# trinamic-controller.net
KiCad netlist of a schematic drawn in Altium Designer
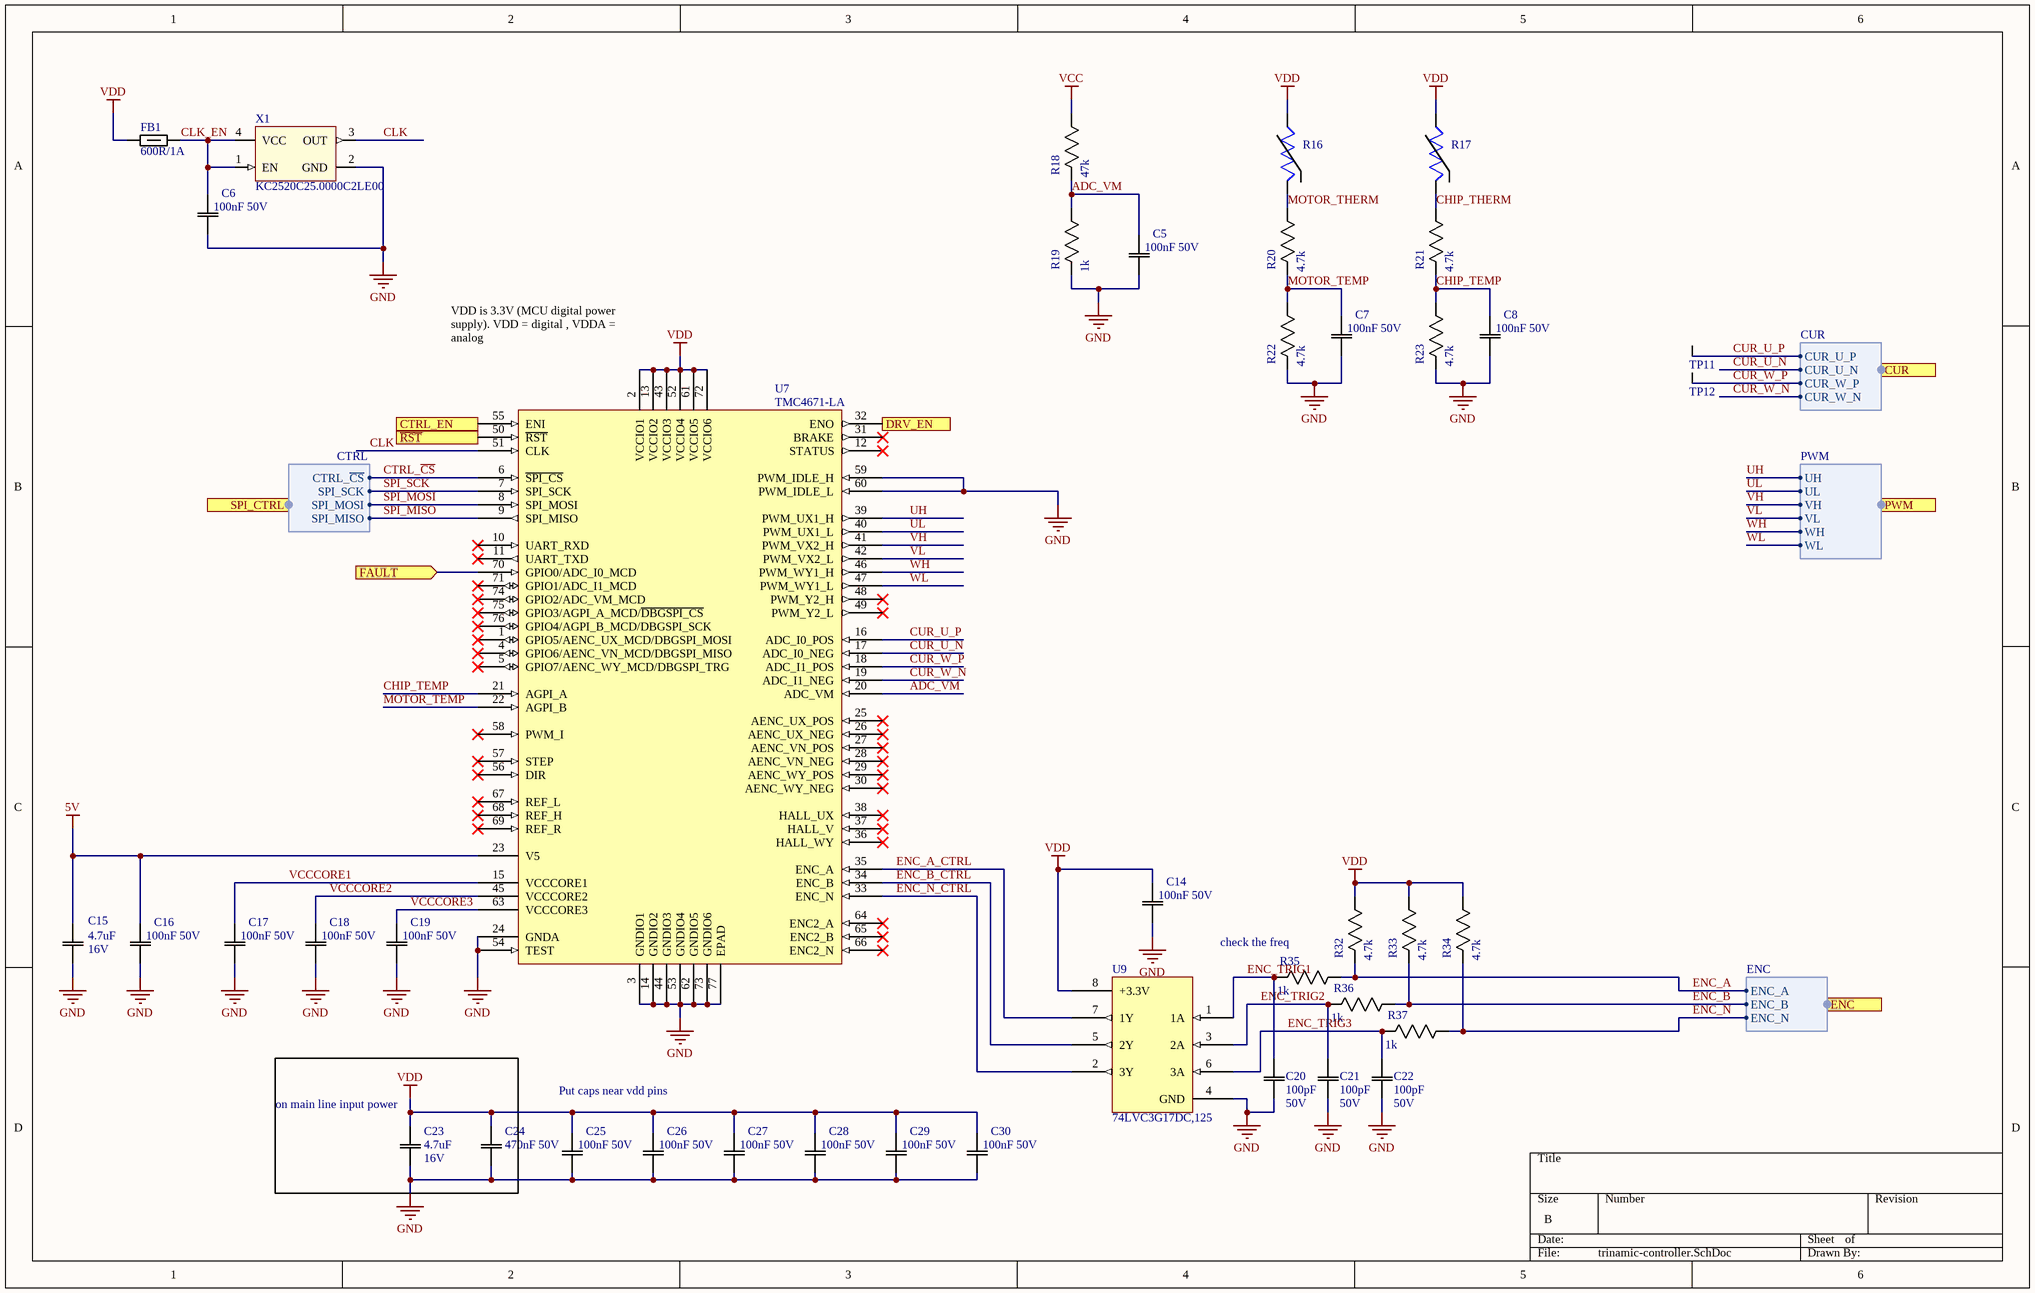
[diagram p0: trinamic-controller.SchDoc]

(export (version "E")
  (design (tool "Eeschema 10.0.6"))
  (components
    (comp (ref "C5")
      (value "100nF 50V")
      (footprint "0603")
      (description "Default Symbol for Capacitors")
      (fields (field (name "TOLERANCE") "10%") (field (name "PART NUMBER") "CAP 100nF 50V"))
      (libsource (lib "capacitor_library") (part "CAP_Default"))
    )
    (comp (ref "C6")
      (value "100nF 50V")
      (footprint "0603")
      (description "Default Symbol for Capacitors")
      (fields (field (name "TOLERANCE") "10%") (field (name "PART NUMBER") "CAP 100nF 50V"))
      (libsource (lib "capacitor_library") (part "CAP_Default"))
    )
    (comp (ref "C7")
      (value "100nF 50V")
      (footprint "0603")
      (description "Default Symbol for Capacitors")
      (fields (field (name "TOLERANCE") "10%") (field (name "PART NUMBER") "CAP 100nF 50V"))
      (libsource (lib "capacitor_library") (part "CAP_Default"))
    )
    (comp (ref "C8")
      (value "100nF 50V")
      (footprint "0603")
      (description "Default Symbol for Capacitors")
      (fields (field (name "TOLERANCE") "10%") (field (name "PART NUMBER") "CAP 100nF 50V"))
      (libsource (lib "capacitor_library") (part "CAP_Default"))
    )
    (comp (ref "C14")
      (value "100nF 50V")
      (footprint "0603")
      (description "Default Symbol for Capacitors")
      (fields (field (name "TOLERANCE") "10%") (field (name "PART NUMBER") "CAP 100nF 50V"))
      (libsource (lib "capacitor_library") (part "CAP_Default"))
    )
    (comp (ref "C15")
      (value "4.7uF")
      (footprint "0603")
      (description "Default Symbol for Capacitors")
      (fields
        (field (name "TOLERANCE") "10%")
        (field (name "RATING") "16V")
        (field (name "PART NUMBER") "CAP 4.7uF 16V")
      )
      (libsource (lib "capacitor_library") (part "CAP_Default"))
    )
    (comp (ref "C16")
      (value "100nF 50V")
      (footprint "0603")
      (description "Default Symbol for Capacitors")
      (fields (field (name "TOLERANCE") "10%") (field (name "PART NUMBER") "CAP 100nF 50V"))
      (libsource (lib "capacitor_library") (part "CAP_Default"))
    )
    (comp (ref "C17")
      (value "100nF 50V")
      (footprint "0603")
      (description "Default Symbol for Capacitors")
      (fields (field (name "TOLERANCE") "10%") (field (name "PART NUMBER") "CAP 100nF 50V"))
      (libsource (lib "capacitor_library") (part "CAP_Default"))
    )
    (comp (ref "C18")
      (value "100nF 50V")
      (footprint "0603")
      (description "Default Symbol for Capacitors")
      (fields (field (name "TOLERANCE") "10%") (field (name "PART NUMBER") "CAP 100nF 50V"))
      (libsource (lib "capacitor_library") (part "CAP_Default"))
    )
    (comp (ref "C19")
      (value "100nF 50V")
      (footprint "0603")
      (description "Default Symbol for Capacitors")
      (fields (field (name "TOLERANCE") "10%") (field (name "PART NUMBER") "CAP 100nF 50V"))
      (libsource (lib "capacitor_library") (part "CAP_Default"))
    )
    (comp (ref "C20")
      (value "100pF")
      (footprint "0603")
      (description "Default Symbol for Capacitors")
      (fields
        (field (name "TOLERANCE") "10%")
        (field (name "RATING") "50V")
        (field (name "PART NUMBER") "CAP 100pF 50V")
      )
      (libsource (lib "capacitor_library") (part "CAP_Default"))
    )
    (comp (ref "C21")
      (value "100pF")
      (footprint "0603")
      (description "Default Symbol for Capacitors")
      (fields
        (field (name "TOLERANCE") "10%")
        (field (name "RATING") "50V")
        (field (name "PART NUMBER") "CAP 100pF 50V")
      )
      (libsource (lib "capacitor_library") (part "CAP_Default"))
    )
    (comp (ref "C22")
      (value "100pF")
      (footprint "0603")
      (description "Default Symbol for Capacitors")
      (fields
        (field (name "TOLERANCE") "10%")
        (field (name "RATING") "50V")
        (field (name "PART NUMBER") "CAP 100pF 50V")
      )
      (libsource (lib "capacitor_library") (part "CAP_Default"))
    )
    (comp (ref "C23")
      (value "4.7uF")
      (footprint "0603")
      (description "Default Symbol for Capacitors")
      (fields
        (field (name "TOLERANCE") "10%")
        (field (name "RATING") "16V")
        (field (name "PART NUMBER") "CAP 4.7uF 16V")
      )
      (libsource (lib "capacitor_library") (part "CAP_Default"))
    )
    (comp (ref "C24")
      (value "470nF 50V")
      (footprint "0603")
      (description "Default Symbol for Capacitors")
      (fields (field (name "TOLERANCE") "10%") (field (name "PART NUMBER") "CAP 470nF 50V"))
      (libsource (lib "capacitor_library") (part "CAP_Default"))
    )
    (comp (ref "C25")
      (value "100nF 50V")
      (footprint "0603")
      (description "Default Symbol for Capacitors")
      (fields (field (name "TOLERANCE") "10%") (field (name "PART NUMBER") "CAP 100nF 50V"))
      (libsource (lib "capacitor_library") (part "CAP_Default"))
    )
    (comp (ref "C26")
      (value "100nF 50V")
      (footprint "0603")
      (description "Default Symbol for Capacitors")
      (fields (field (name "TOLERANCE") "10%") (field (name "PART NUMBER") "CAP 100nF 50V"))
      (libsource (lib "capacitor_library") (part "CAP_Default"))
    )
    (comp (ref "C27")
      (value "100nF 50V")
      (footprint "0603")
      (description "Default Symbol for Capacitors")
      (fields (field (name "TOLERANCE") "10%") (field (name "PART NUMBER") "CAP 100nF 50V"))
      (libsource (lib "capacitor_library") (part "CAP_Default"))
    )
    (comp (ref "C28")
      (value "100nF 50V")
      (footprint "0603")
      (description "Default Symbol for Capacitors")
      (fields (field (name "TOLERANCE") "10%") (field (name "PART NUMBER") "CAP 100nF 50V"))
      (libsource (lib "capacitor_library") (part "CAP_Default"))
    )
    (comp (ref "C29")
      (value "100nF 50V")
      (footprint "0603")
      (description "Default Symbol for Capacitors")
      (fields (field (name "TOLERANCE") "10%") (field (name "PART NUMBER") "CAP 100nF 50V"))
      (libsource (lib "capacitor_library") (part "CAP_Default"))
    )
    (comp (ref "C30")
      (value "100nF 50V")
      (footprint "0603")
      (description "Default Symbol for Capacitors")
      (fields (field (name "TOLERANCE") "10%") (field (name "PART NUMBER") "CAP 100nF 50V"))
      (libsource (lib "capacitor_library") (part "CAP_Default"))
    )
    (comp (ref "FB1")
      (value "600R/1A")
      (footprint "0603")
      (fields (field (name "PART NUMBER") "FERRITE BEAD 200 MOHM 0603 1LN"))
      (libsource (lib "Inductor_Library") (part "FERRITE BEAD 200 MOHM 0603 1LN"))
    )
    (comp (ref "R16")
      (value "RES NTC 10k")
      (footprint "THERMISTOR TH")
      (fields (field (name "PART NUMBER") "RES NTC 10k TH") (field (name "TOLERANCE") "1%"))
      (libsource (lib "Resistor_Library") (part "RES NTC 10k"))
    )
    (comp (ref "R17")
      (value "RES NTC 10k")
      (footprint "0603")
      (fields (field (name "PART NUMBER") "RES NTC 10k CHIP") (field (name "TOLERANCE") "1%"))
      (libsource (lib "Resistor_Library") (part "RES NTC 10k"))
    )
    (comp (ref "R18")
      (value "47k")
      (footprint "0603")
      (description "Default Resistor Symbol")
      (fields (field (name "TOLERANCE") "1%") (field (name "PART NUMBER") "RES 47k 1/8W - 1%"))
      (libsource (lib "Resistor_Library") (part "RES_DEFAULT"))
    )
    (comp (ref "R19")
      (value "1k")
      (footprint "0603")
      (description "Default Resistor Symbol")
      (fields (field (name "TOLERANCE") "1%") (field (name "PART NUMBER") "RES 1k 1/8W - 1%"))
      (libsource (lib "") (part "RES_DEFAULT_1"))
    )
    (comp (ref "R20")
      (value "4.7k")
      (footprint "0603")
      (description "Default Resistor Symbol")
      (fields (field (name "TOLERANCE") "1%") (field (name "PART NUMBER") "RES 4.7k 1/8W - 1%"))
      (libsource (lib "Resistor_Library") (part "RES_DEFAULT"))
    )
    (comp (ref "R21")
      (value "4.7k")
      (footprint "0603")
      (description "Default Resistor Symbol")
      (fields (field (name "TOLERANCE") "1%") (field (name "PART NUMBER") "RES 4.7k 1/8W - 1%"))
      (libsource (lib "Resistor_Library") (part "RES_DEFAULT"))
    )
    (comp (ref "R22")
      (value "4.7k")
      (footprint "0603")
      (description "Default Resistor Symbol")
      (fields (field (name "TOLERANCE") "1%") (field (name "PART NUMBER") "RES 4.7k 1/8W - 1%"))
      (libsource (lib "Resistor_Library") (part "RES_DEFAULT"))
    )
    (comp (ref "R23")
      (value "4.7k")
      (footprint "0603")
      (description "Default Resistor Symbol")
      (fields (field (name "TOLERANCE") "1%") (field (name "PART NUMBER") "RES 4.7k 1/8W - 1%"))
      (libsource (lib "Resistor_Library") (part "RES_DEFAULT"))
    )
    (comp (ref "R32")
      (value "4.7k")
      (footprint "0603")
      (description "Default Resistor Symbol")
      (fields (field (name "TOLERANCE") "5%") (field (name "PART NUMBER") "RES 4.7k 1/8W - 5%"))
      (libsource (lib "") (part "RES_DEFAULT_1"))
    )
    (comp (ref "R33")
      (value "4.7k")
      (footprint "0603")
      (description "Default Resistor Symbol")
      (fields (field (name "TOLERANCE") "5%") (field (name "PART NUMBER") "RES 4.7k 1/8W - 5%"))
      (libsource (lib "") (part "RES_DEFAULT_1"))
    )
    (comp (ref "R34")
      (value "4.7k")
      (footprint "0603")
      (description "Default Resistor Symbol")
      (fields (field (name "TOLERANCE") "5%") (field (name "PART NUMBER") "RES 4.7k 1/8W - 5%"))
      (libsource (lib "Resistor_Library") (part "RES_DEFAULT"))
    )
    (comp (ref "R35")
      (value "1k")
      (footprint "0603")
      (description "Default Resistor Symbol")
      (fields (field (name "TOLERANCE") "1%") (field (name "PART NUMBER") "RES 1k 1/8W - 1%"))
      (libsource (lib "Resistor_Library") (part "RES_DEFAULT"))
    )
    (comp (ref "R36")
      (value "1k")
      (footprint "0603")
      (description "Default Resistor Symbol")
      (fields (field (name "TOLERANCE") "1%") (field (name "PART NUMBER") "RES 1k 1/8W - 1%"))
      (libsource (lib "") (part "RES_DEFAULT_1"))
    )
    (comp (ref "R37")
      (value "1k")
      (footprint "0603")
      (description "Default Resistor Symbol")
      (fields (field (name "TOLERANCE") "1%") (field (name "PART NUMBER") "RES 1k 1/8W - 1%"))
      (libsource (lib "Resistor_Library") (part "RES_DEFAULT"))
    )
    (comp (ref "TP11")
      (value "C_U")
      (footprint "TP")
      (fields (field (name "PART NUMBER") "Test Point (Via)"))
      (libsource (lib "IC_Library") (part "Test Point (Via)"))
    )
    (comp (ref "TP12")
      (value "C_W")
      (footprint "TP")
      (fields (field (name "PART NUMBER") "Test Point (Via)"))
      (libsource (lib "IC_Library") (part "Test Point (Via)"))
    )
    (comp (ref "U7")
      (value "TMC4671-LA")
      (footprint "QFN40P1050X650X90_HS-77N")
      (description "Motor Driver, -40 To 125Deg C Rohs Compliant: Yes")
      (fields (field (name "PART NUMBER") "TMC4671"))
      (libsource (lib "IC_Library") (part "TMC4671"))
    )
    (comp (ref "U9")
      (value "74LVC3G17DC,125")
      (footprint "8-VSSOP")
      (description "IC BUFFER TRIPLE SCHMITT TRIGGER 5.5V VSSOP-8")
      (fields (field (name "PART NUMBER") "IC 74LVC3G17DC,125"))
      (libsource (lib "IC_Library") (part "IC 74LVC3G17DC,125"))
    )
    (comp (ref "X1")
      (value "KC2520C25.0000C2LE00")
      (footprint "KC2520C25.0000C2LE00")
      (description "Oscillator XO 25MHz ±15ppm 15pF CMOS 55% 2.5V/3.3V 4-Pin Mini-CSMD T/R")
      (fields (field (name "PART NUMBER") "XTAL OSC 25MHz 3.3V"))
      (libsource (lib "Oscillator_Library") (part "XTAL OSC 25MHz 3.3V"))
    )
  )
  (nets
    (net (code "5") (name "/ADC_VM") (class "Default")
      (node (ref "C5") (pin "2") (pinfunction "C2_2") (pintype "passive"))
      (node (ref "R18") (pin "2") (pinfunction "R2_2") (pintype "passive"))
      (node (ref "R19") (pin "1") (pinfunction "R1_1") (pintype "passive"))
      (node (ref "U7") (pin "20") (pinfunction "ADC_VM_20") (pintype "input"))
    )
    (net (code "6") (name "/CHIP_TEMP") (class "Default")
      (node (ref "C8") (pin "2") (pinfunction "C2_2") (pintype "passive"))
      (node (ref "R21") (pin "2") (pinfunction "R2_2") (pintype "passive"))
      (node (ref "R23") (pin "1") (pinfunction "R1_1") (pintype "passive"))
      (node (ref "U7") (pin "21") (pinfunction "AGPI_A_21") (pintype "input"))
    )
    (net (code "7") (name "/CHIP_THERM") (class "Default")
      (node (ref "R17") (pin "1") (pinfunction "1_1") (pintype "passive"))
      (node (ref "R21") (pin "1") (pinfunction "R1_1") (pintype "passive"))
    )
    (net (code "8") (name "/CLK") (class "Default")
      (node (ref "U7") (pin "51") (pinfunction "CLK_51") (pintype "input"))
      (node (ref "X1") (pin "3") (pinfunction "OUT_3") (pintype "output"))
    )
    (net (code "9") (name "/CLK_EN") (class "Default")
      (node (ref "C6") (pin "2") (pinfunction "C2_2") (pintype "passive"))
      (node (ref "FB1") (pin "2") (pinfunction "2_2") (pintype "passive"))
      (node (ref "X1") (pin "1") (pinfunction "EN_1") (pintype "input"))
      (node (ref "X1") (pin "4") (pinfunction "VCC_4") (pintype "power_in"))
    )
    (net (code "10") (name "/CTRL_EN") (class "Default")
      (node (ref "U7") (pin "55") (pinfunction "ENI_55") (pintype "input"))
    )
    (net (code "11") (name "/CTRL_~{CS}") (class "Default")
      (node (ref "U7") (pin "6") (pinfunction "~{SPI_CS}_6") (pintype "input"))
    )
    (net (code "12") (name "/CUR_U_N") (class "Default")
      (node (ref "U7") (pin "17") (pinfunction "ADC_I0_NEG_17") (pintype "input"))
    )
    (net (code "13") (name "/CUR_U_P") (class "Default")
      (node (ref "TP11") (pin "1") (pinfunction "1_1") (pintype "passive"))
      (node (ref "U7") (pin "16") (pinfunction "ADC_I0_POS_16") (pintype "input"))
    )
    (net (code "14") (name "/CUR_W_N") (class "Default")
      (node (ref "U7") (pin "19") (pinfunction "ADC_I1_NEG_19") (pintype "input"))
    )
    (net (code "15") (name "/CUR_W_P") (class "Default")
      (node (ref "TP12") (pin "1") (pinfunction "1_1") (pintype "passive"))
      (node (ref "U7") (pin "18") (pinfunction "ADC_I1_POS_18") (pintype "input"))
    )
    (net (code "16") (name "/DRV_EN") (class "Default")
      (node (ref "U7") (pin "32") (pinfunction "ENO_32") (pintype "output"))
    )
    (net (code "17") (name "/ENC_A") (class "Default")
      (node (ref "R32") (pin "2") (pinfunction "R2_2") (pintype "passive"))
      (node (ref "R35") (pin "1") (pinfunction "R1_1") (pintype "passive"))
    )
    (net (code "18") (name "/ENC_A_CTRL") (class "Default")
      (node (ref "U7") (pin "35") (pinfunction "ENC_A_35") (pintype "input"))
      (node (ref "U9") (pin "7") (pinfunction "1Y_7") (pintype "output"))
    )
    (net (code "19") (name "/ENC_B") (class "Default")
      (node (ref "R33") (pin "2") (pinfunction "R2_2") (pintype "passive"))
      (node (ref "R36") (pin "1") (pinfunction "R1_1") (pintype "passive"))
    )
    (net (code "20") (name "/ENC_B_CTRL") (class "Default")
      (node (ref "U7") (pin "34") (pinfunction "ENC_B_34") (pintype "input"))
      (node (ref "U9") (pin "5") (pinfunction "2Y_5") (pintype "output"))
    )
    (net (code "21") (name "/ENC_N") (class "Default")
      (node (ref "R34") (pin "2") (pinfunction "R2_2") (pintype "passive"))
      (node (ref "R37") (pin "1") (pinfunction "R1_1") (pintype "passive"))
    )
    (net (code "22") (name "/ENC_N_CTRL") (class "Default")
      (node (ref "U7") (pin "33") (pinfunction "ENC_N_33") (pintype "input"))
      (node (ref "U9") (pin "2") (pinfunction "3Y_2") (pintype "output"))
    )
    (net (code "23") (name "/ENC_TRIG1") (class "Default")
      (node (ref "C20") (pin "2") (pinfunction "C2_2") (pintype "passive"))
      (node (ref "R35") (pin "2") (pinfunction "R2_2") (pintype "passive"))
      (node (ref "U9") (pin "1") (pinfunction "1A_1") (pintype "input"))
    )
    (net (code "24") (name "/ENC_TRIG2") (class "Default")
      (node (ref "C21") (pin "2") (pinfunction "C2_2") (pintype "passive"))
      (node (ref "R36") (pin "2") (pinfunction "R2_2") (pintype "passive"))
      (node (ref "U9") (pin "3") (pinfunction "2A_3") (pintype "input"))
    )
    (net (code "25") (name "/ENC_TRIG3") (class "Default")
      (node (ref "C22") (pin "2") (pinfunction "C2_2") (pintype "passive"))
      (node (ref "R37") (pin "2") (pinfunction "R2_2") (pintype "passive"))
      (node (ref "U9") (pin "6") (pinfunction "3A_6") (pintype "input"))
    )
    (net (code "26") (name "/FAULT") (class "Default")
      (node (ref "U7") (pin "70") (pinfunction "GPIO0/ADC_I0_MCD_70") (pintype "input"))
    )
    (net (code "27") (name "/MOTOR_TEMP") (class "Default")
      (node (ref "C7") (pin "2") (pinfunction "C2_2") (pintype "passive"))
      (node (ref "R20") (pin "2") (pinfunction "R2_2") (pintype "passive"))
      (node (ref "R22") (pin "1") (pinfunction "R1_1") (pintype "passive"))
      (node (ref "U7") (pin "22") (pinfunction "AGPI_B_22") (pintype "input"))
    )
    (net (code "28") (name "/MOTOR_THERM") (class "Default")
      (node (ref "R16") (pin "1") (pinfunction "1_1") (pintype "passive"))
      (node (ref "R20") (pin "1") (pinfunction "R1_1") (pintype "passive"))
    )
    (net (code "29") (name "/SPI_MISO") (class "Default")
      (node (ref "U7") (pin "9") (pinfunction "SPI_MISO_9") (pintype "output"))
    )
    (net (code "30") (name "/SPI_MOSI") (class "Default")
      (node (ref "U7") (pin "8") (pinfunction "SPI_MOSI_8") (pintype "input"))
    )
    (net (code "31") (name "/SPI_SCK") (class "Default")
      (node (ref "U7") (pin "7") (pinfunction "SPI_SCK_7") (pintype "input"))
    )
    (net (code "32") (name "/UH") (class "Default")
      (node (ref "U7") (pin "39") (pinfunction "PWM_UX1_H_39") (pintype "output"))
    )
    (net (code "33") (name "/UL") (class "Default")
      (node (ref "U7") (pin "40") (pinfunction "PWM_UX1_L_40") (pintype "output"))
    )
    (net (code "34") (name "/VCCCORE1") (class "Default")
      (node (ref "C17") (pin "2") (pinfunction "C2_2") (pintype "passive"))
      (node (ref "U7") (pin "15") (pinfunction "VCCCORE1_15") (pintype "power_in"))
    )
    (net (code "35") (name "/VCCCORE2") (class "Default")
      (node (ref "C18") (pin "2") (pinfunction "C2_2") (pintype "passive"))
      (node (ref "U7") (pin "45") (pinfunction "VCCCORE2_45") (pintype "power_in"))
    )
    (net (code "36") (name "/VCCCORE3") (class "Default")
      (node (ref "C19") (pin "2") (pinfunction "C2_2") (pintype "passive"))
      (node (ref "U7") (pin "63") (pinfunction "VCCCORE3_63") (pintype "power_in"))
    )
    (net (code "37") (name "/VH") (class "Default")
      (node (ref "U7") (pin "41") (pinfunction "PWM_VX2_H_41") (pintype "output"))
    )
    (net (code "38") (name "/VL") (class "Default")
      (node (ref "U7") (pin "42") (pinfunction "PWM_VX2_L_42") (pintype "output"))
    )
    (net (code "39") (name "/WH") (class "Default")
      (node (ref "U7") (pin "46") (pinfunction "PWM_WY1_H_46") (pintype "output"))
    )
    (net (code "40") (name "/WL") (class "Default")
      (node (ref "U7") (pin "47") (pinfunction "PWM_WY1_L_47") (pintype "output"))
    )
    (net (code "45") (name "/~{RST}") (class "Default")
      (node (ref "U7") (pin "50") (pinfunction "~{RST}_50") (pintype "input"))
    )
    (net (code "46") (name "5V") (class "Default")
      (node (ref "C15") (pin "2") (pinfunction "C2_2") (pintype "passive"))
      (node (ref "C16") (pin "2") (pinfunction "C2_2") (pintype "passive"))
      (node (ref "U7") (pin "23") (pinfunction "V5_23") (pintype "power_in"))
    )
    (net (code "47") (name "GND") (class "Default")
      (node (ref "C14") (pin "1") (pinfunction "C1_1") (pintype "passive"))
      (node (ref "C15") (pin "1") (pinfunction "C1_1") (pintype "passive"))
      (node (ref "C16") (pin "1") (pinfunction "C1_1") (pintype "passive"))
      (node (ref "C17") (pin "1") (pinfunction "C1_1") (pintype "passive"))
      (node (ref "C18") (pin "1") (pinfunction "C1_1") (pintype "passive"))
      (node (ref "C19") (pin "1") (pinfunction "C1_1") (pintype "passive"))
      (node (ref "C20") (pin "1") (pinfunction "C1_1") (pintype "passive"))
      (node (ref "C21") (pin "1") (pinfunction "C1_1") (pintype "passive"))
      (node (ref "C22") (pin "1") (pinfunction "C1_1") (pintype "passive"))
      (node (ref "C23") (pin "1") (pinfunction "C1_1") (pintype "passive"))
      (node (ref "C24") (pin "1") (pinfunction "C1_1") (pintype "passive"))
      (node (ref "C25") (pin "1") (pinfunction "C1_1") (pintype "passive"))
      (node (ref "C26") (pin "1") (pinfunction "C1_1") (pintype "passive"))
      (node (ref "C27") (pin "1") (pinfunction "C1_1") (pintype "passive"))
      (node (ref "C28") (pin "1") (pinfunction "C1_1") (pintype "passive"))
      (node (ref "C29") (pin "1") (pinfunction "C1_1") (pintype "passive"))
      (node (ref "C30") (pin "1") (pinfunction "C1_1") (pintype "passive"))
      (node (ref "C5") (pin "1") (pinfunction "C1_1") (pintype "passive"))
      (node (ref "C6") (pin "1") (pinfunction "C1_1") (pintype "passive"))
      (node (ref "C7") (pin "1") (pinfunction "C1_1") (pintype "passive"))
      (node (ref "C8") (pin "1") (pinfunction "C1_1") (pintype "passive"))
      (node (ref "R19") (pin "2") (pinfunction "R2_2") (pintype "passive"))
      (node (ref "R22") (pin "2") (pinfunction "R2_2") (pintype "passive"))
      (node (ref "R23") (pin "2") (pinfunction "R2_2") (pintype "passive"))
      (node (ref "U7") (pin "14") (pinfunction "GNDIO2_14") (pintype "power_in"))
      (node (ref "U7") (pin "24") (pinfunction "GNDA_24") (pintype "power_in"))
      (node (ref "U7") (pin "3") (pinfunction "GNDIO1_3") (pintype "power_in"))
      (node (ref "U7") (pin "44") (pinfunction "GNDIO3_44") (pintype "power_in"))
      (node (ref "U7") (pin "53") (pinfunction "GNDIO4_53") (pintype "power_in"))
      (node (ref "U7") (pin "54") (pinfunction "TEST_54") (pintype "input"))
      (node (ref "U7") (pin "59") (pinfunction "PWM_IDLE_H_59") (pintype "input"))
      (node (ref "U7") (pin "60") (pinfunction "PWM_IDLE_L_60") (pintype "input"))
      (node (ref "U7") (pin "62") (pinfunction "GNDIO5_62") (pintype "power_in"))
      (node (ref "U7") (pin "73") (pinfunction "GNDIO6_73") (pintype "power_in"))
      (node (ref "U7") (pin "77") (pinfunction "EPAD_77") (pintype "passive"))
      (node (ref "U9") (pin "4") (pinfunction "GND_4") (pintype "power_in"))
      (node (ref "X1") (pin "2") (pinfunction "GND_2") (pintype "power_in"))
    )
    (net (code "48") (name "VCC") (class "Default")
      (node (ref "R18") (pin "1") (pinfunction "R1_1") (pintype "passive"))
    )
    (net (code "49") (name "VDD") (class "Default")
      (node (ref "C14") (pin "2") (pinfunction "C2_2") (pintype "passive"))
      (node (ref "C23") (pin "2") (pinfunction "C2_2") (pintype "passive"))
      (node (ref "C24") (pin "2") (pinfunction "C2_2") (pintype "passive"))
      (node (ref "C25") (pin "2") (pinfunction "C2_2") (pintype "passive"))
      (node (ref "C26") (pin "2") (pinfunction "C2_2") (pintype "passive"))
      (node (ref "C27") (pin "2") (pinfunction "C2_2") (pintype "passive"))
      (node (ref "C28") (pin "2") (pinfunction "C2_2") (pintype "passive"))
      (node (ref "C29") (pin "2") (pinfunction "C2_2") (pintype "passive"))
      (node (ref "C30") (pin "2") (pinfunction "C2_2") (pintype "passive"))
      (node (ref "FB1") (pin "1") (pinfunction "1_1") (pintype "passive"))
      (node (ref "R16") (pin "2") (pinfunction "2_2") (pintype "passive"))
      (node (ref "R17") (pin "2") (pinfunction "2_2") (pintype "passive"))
      (node (ref "R32") (pin "1") (pinfunction "R1_1") (pintype "passive"))
      (node (ref "R33") (pin "1") (pinfunction "R1_1") (pintype "passive"))
      (node (ref "R34") (pin "1") (pinfunction "R1_1") (pintype "passive"))
      (node (ref "U7") (pin "13") (pinfunction "VCCIO2_13") (pintype "power_in"))
      (node (ref "U7") (pin "2") (pinfunction "VCCIO1_2") (pintype "power_in"))
      (node (ref "U7") (pin "43") (pinfunction "VCCIO3_43") (pintype "power_in"))
      (node (ref "U7") (pin "52") (pinfunction "VCCIO4_52") (pintype "power_in"))
      (node (ref "U7") (pin "61") (pinfunction "VCCIO5_61") (pintype "power_in"))
      (node (ref "U7") (pin "72") (pinfunction "VCCIO6_72") (pintype "power_in"))
      (node (ref "U9") (pin "8") (pinfunction "+3.3V_8") (pintype "power_in"))
    )
    (net (code "50") (name "unconnected-(U7-AENC_UX_NEG-Pad26)") (class "Default")
      (node (ref "U7") (pin "26") (pinfunction "AENC_UX_NEG_26") (pintype "input+no_connect"))
    )
    (net (code "51") (name "unconnected-(U7-AENC_UX_POS-Pad25)") (class "Default")
      (node (ref "U7") (pin "25") (pinfunction "AENC_UX_POS_25") (pintype "input+no_connect"))
    )
    (net (code "52") (name "unconnected-(U7-AENC_VN_NEG-Pad28)") (class "Default")
      (node (ref "U7") (pin "28") (pinfunction "AENC_VN_NEG_28") (pintype "input+no_connect"))
    )
    (net (code "53") (name "unconnected-(U7-AENC_VN_POS-Pad27)") (class "Default")
      (node (ref "U7") (pin "27") (pinfunction "AENC_VN_POS_27") (pintype "input+no_connect"))
    )
    (net (code "54") (name "unconnected-(U7-AENC_WY_NEG-Pad30)") (class "Default")
      (node (ref "U7") (pin "30") (pinfunction "AENC_WY_NEG_30") (pintype "input+no_connect"))
    )
    (net (code "55") (name "unconnected-(U7-AENC_WY_POS-Pad29)") (class "Default")
      (node (ref "U7") (pin "29") (pinfunction "AENC_WY_POS_29") (pintype "input+no_connect"))
    )
    (net (code "56") (name "unconnected-(U7-BRAKE-Pad31)") (class "Default")
      (node (ref "U7") (pin "31") (pinfunction "BRAKE_31") (pintype "output+no_connect"))
    )
    (net (code "57") (name "unconnected-(U7-DIR-Pad56)") (class "Default")
      (node (ref "U7") (pin "56") (pinfunction "DIR_56") (pintype "input+no_connect"))
    )
    (net (code "58") (name "unconnected-(U7-ENC2_A-Pad64)") (class "Default")
      (node (ref "U7") (pin "64") (pinfunction "ENC2_A_64") (pintype "input+no_connect"))
    )
    (net (code "59") (name "unconnected-(U7-ENC2_B-Pad65)") (class "Default")
      (node (ref "U7") (pin "65") (pinfunction "ENC2_B_65") (pintype "input+no_connect"))
    )
    (net (code "60") (name "unconnected-(U7-ENC2_N-Pad66)") (class "Default")
      (node (ref "U7") (pin "66") (pinfunction "ENC2_N_66") (pintype "input+no_connect"))
    )
    (net (code "61") (name "unconnected-(U7-GPIO1{slash}ADC_I1_MCD-Pad71)") (class "Default")
      (node (ref "U7") (pin "71") (pinfunction "GPIO1/ADC_I1_MCD_71") (pintype "bidirectional+no_connect"))
    )
    (net (code "62") (name "unconnected-(U7-GPIO2{slash}ADC_VM_MCD-Pad74)") (class "Default")
      (node (ref "U7") (pin "74") (pinfunction "GPIO2/ADC_VM_MCD_74") (pintype "bidirectional+no_connect"))
    )
    (net (code "63") (name "unconnected-(U7-GPIO3{slash}AGPI_A_MCD{slash}~{DBGSPI_CS}-Pad75)") (class "Default")
      (node (ref "U7") (pin "75") (pinfunction "GPIO3/AGPI_A_MCD/~{DBGSPI_CS}_75") (pintype "bidirectional+no_connect"))
    )
    (net (code "64") (name "unconnected-(U7-GPIO4{slash}AGPI_B_MCD{slash}DBGSPI_SCK-Pad76)") (class "Default")
      (node (ref "U7") (pin "76") (pinfunction "GPIO4/AGPI_B_MCD/DBGSPI_SCK_76") (pintype "bidirectional+no_connect"))
    )
    (net (code "65") (name "unconnected-(U7-GPIO5{slash}AENC_UX_MCD{slash}DBGSPI_MOSI-Pad1)") (class "Default")
      (node (ref "U7") (pin "1") (pinfunction "GPIO5/AENC_UX_MCD/DBGSPI_MOSI_1") (pintype "bidirectional+no_connect"))
    )
    (net (code "66") (name "unconnected-(U7-GPIO6{slash}AENC_VN_MCD{slash}DBGSPI_MISO-Pad4)") (class "Default")
      (node (ref "U7") (pin "4") (pinfunction "GPIO6/AENC_VN_MCD/DBGSPI_MISO_4") (pintype "bidirectional+no_connect"))
    )
    (net (code "67") (name "unconnected-(U7-GPIO7{slash}AENC_WY_MCD{slash}DBGSPI_TRG-Pad5)") (class "Default")
      (node (ref "U7") (pin "5") (pinfunction "GPIO7/AENC_WY_MCD/DBGSPI_TRG_5") (pintype "bidirectional+no_connect"))
    )
    (net (code "68") (name "unconnected-(U7-HALL_UX-Pad38)") (class "Default")
      (node (ref "U7") (pin "38") (pinfunction "HALL_UX_38") (pintype "input+no_connect"))
    )
    (net (code "69") (name "unconnected-(U7-HALL_V-Pad37)") (class "Default")
      (node (ref "U7") (pin "37") (pinfunction "HALL_V_37") (pintype "input+no_connect"))
    )
    (net (code "70") (name "unconnected-(U7-HALL_WY-Pad36)") (class "Default")
      (node (ref "U7") (pin "36") (pinfunction "HALL_WY_36") (pintype "input+no_connect"))
    )
    (net (code "71") (name "unconnected-(U7-PWM_I-Pad58)") (class "Default")
      (node (ref "U7") (pin "58") (pinfunction "PWM_I_58") (pintype "input+no_connect"))
    )
    (net (code "72") (name "unconnected-(U7-PWM_Y2_H-Pad48)") (class "Default")
      (node (ref "U7") (pin "48") (pinfunction "PWM_Y2_H_48") (pintype "output+no_connect"))
    )
    (net (code "73") (name "unconnected-(U7-PWM_Y2_L-Pad49)") (class "Default")
      (node (ref "U7") (pin "49") (pinfunction "PWM_Y2_L_49") (pintype "output+no_connect"))
    )
    (net (code "74") (name "unconnected-(U7-REF_H-Pad68)") (class "Default")
      (node (ref "U7") (pin "68") (pinfunction "REF_H_68") (pintype "input+no_connect"))
    )
    (net (code "75") (name "unconnected-(U7-REF_L-Pad67)") (class "Default")
      (node (ref "U7") (pin "67") (pinfunction "REF_L_67") (pintype "input+no_connect"))
    )
    (net (code "76") (name "unconnected-(U7-REF_R-Pad69)") (class "Default")
      (node (ref "U7") (pin "69") (pinfunction "REF_R_69") (pintype "input+no_connect"))
    )
    (net (code "77") (name "unconnected-(U7-STATUS-Pad12)") (class "Default")
      (node (ref "U7") (pin "12") (pinfunction "STATUS_12") (pintype "output+no_connect"))
    )
    (net (code "78") (name "unconnected-(U7-STEP-Pad57)") (class "Default")
      (node (ref "U7") (pin "57") (pinfunction "STEP_57") (pintype "input+no_connect"))
    )
    (net (code "79") (name "unconnected-(U7-UART_RXD-Pad10)") (class "Default")
      (node (ref "U7") (pin "10") (pinfunction "UART_RXD_10") (pintype "input+no_connect"))
    )
    (net (code "80") (name "unconnected-(U7-UART_TXD-Pad11)") (class "Default")
      (node (ref "U7") (pin "11") (pinfunction "UART_TXD_11") (pintype "output+no_connect"))
    )
  )
)
